# 01_BQ25895_BMS.net
KiCad netlist of a schematic drawn in Altium Designer
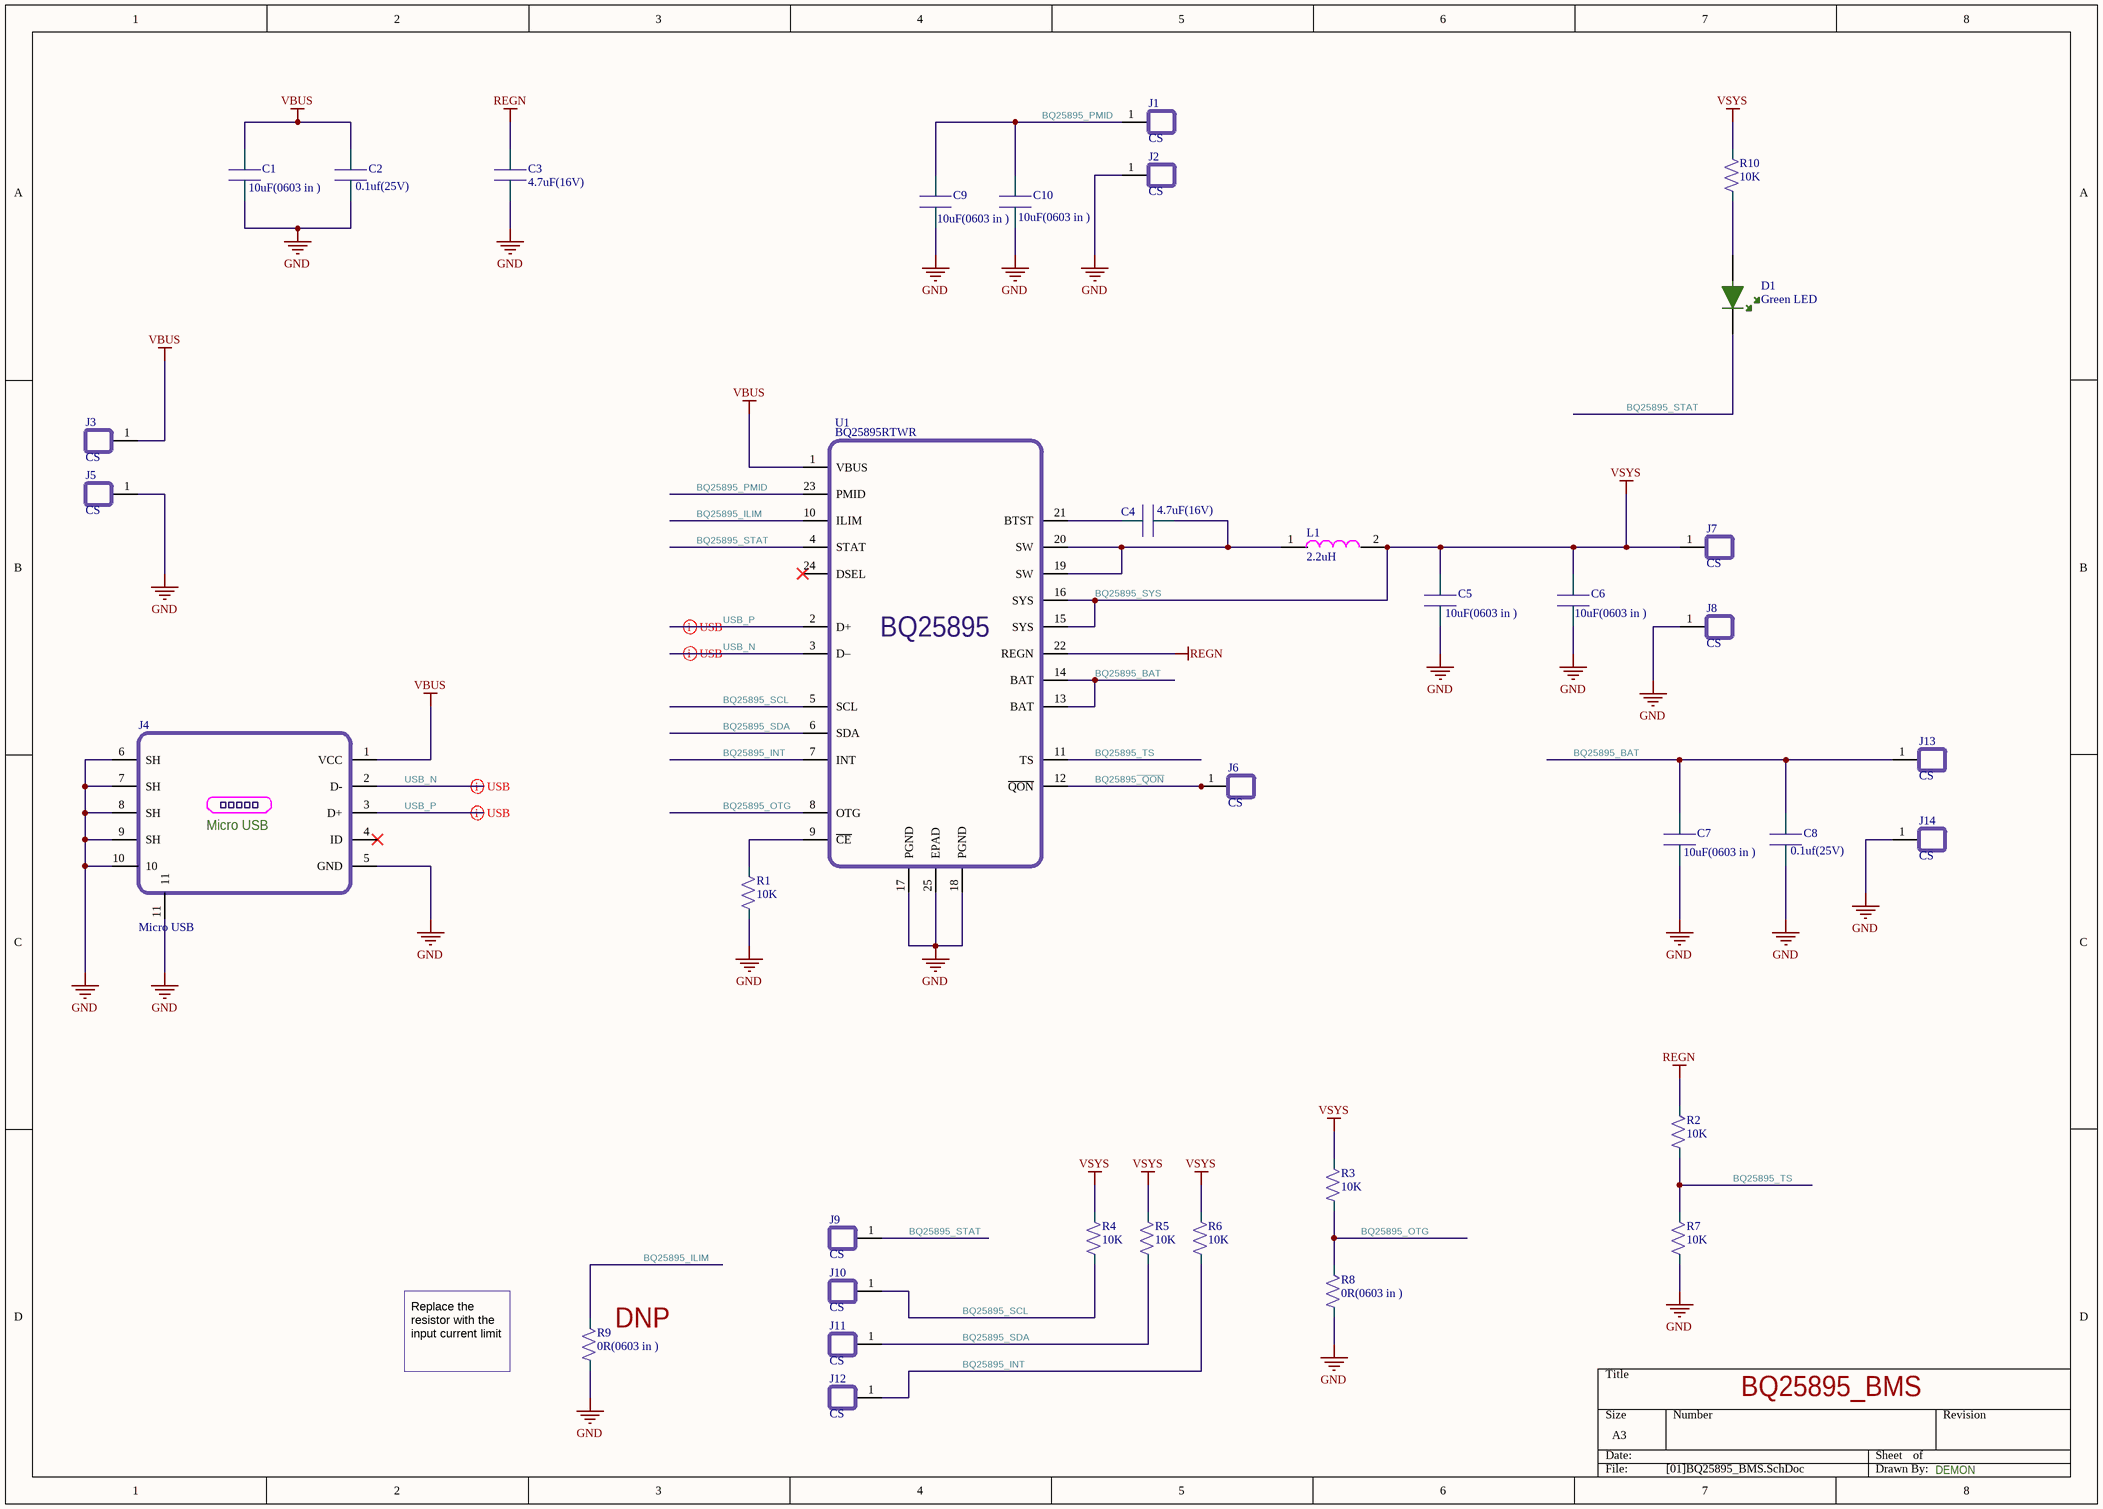
[diagram p0: [01]BQ25895_BMS.SchDoc]

(export (version "E")
  (design (tool "Eeschema 10.0.6"))
  (components
    (comp (ref "C1")
      (value "10uF(0603 in )")
      (footprint "Capacitor_0603")
      (description "10µF ±10% 25V Ceramic Capacitor X5R 0603 (1608 Metric)")
      (fields
        (field (name "MANUFACTURERPARTNUMBER") "GRM188R61E106KA73D")
        (field (name "MANUFACTURER") "Murata Electronics")
      )
      (libsource (lib "Capacitors") (part "GRM188R61E106KA73D"))
    )
    (comp (ref "C2")
      (value "0.1uf(25V)")
      (footprint "Capacitor_0603")
      (description "±5% 25V Ceramic Capacitor X7R 0603 (1608 Metric)")
      (fields
        (field (name "MANUFACTURERPARTNUMBER") "C0603C104J3RAC7411")
        (field (name "MANUFACTURER") "KEMET")
      )
      (libsource (lib "Capacitors") (part "C0603C104J3RAC7411"))
    )
    (comp (ref "C3")
      (value "4.7uF(16V)")
      (footprint "Capacitor_0603")
      (description "4.7µF ±10% 16V Ceramic Capacitor X7S 0603 (1608 Metric)")
      (fields
        (field (name "MANUFACTURERPARTNUMBER") "GRM188C71C475KE21D")
        (field (name "MANUFACTURER") "Murata Electronics")
      )
      (libsource (lib "Capacitors") (part "GRM188C71C475KE21D"))
    )
    (comp (ref "C4")
      (value "4.7uF(16V)")
      (footprint "CAPACITOR_0402")
      (description "4.7µF ±20% 16V Ceramic Capacitor X5R 0402 (1005 Metric)")
      (fields
        (field (name "MANUFACTURERPARTNUMBER") "0402YD475MAT2A")
        (field (name "MANUFACTURER") "AVX Corporation")
      )
      (libsource (lib "Capacitors") (part "0402YD475MAT2A"))
    )
    (comp (ref "C5")
      (value "10uF(0603 in )")
      (footprint "Capacitor_0603")
      (description "10µF ±10% 25V Ceramic Capacitor X5R 0603 (1608 Metric)")
      (fields
        (field (name "MANUFACTURERPARTNUMBER") "GRM188R61E106KA73D")
        (field (name "MANUFACTURER") "Murata Electronics")
      )
      (libsource (lib "Capacitors") (part "GRM188R61E106KA73D"))
    )
    (comp (ref "C6")
      (value "10uF(0603 in )")
      (footprint "Capacitor_0603")
      (description "10µF ±10% 25V Ceramic Capacitor X5R 0603 (1608 Metric)")
      (fields
        (field (name "MANUFACTURERPARTNUMBER") "GRM188R61E106KA73D")
        (field (name "MANUFACTURER") "Murata Electronics")
      )
      (libsource (lib "Capacitors") (part "GRM188R61E106KA73D"))
    )
    (comp (ref "C7")
      (value "10uF(0603 in )")
      (footprint "Capacitor_0603")
      (description "10µF ±10% 25V Ceramic Capacitor X5R 0603 (1608 Metric)")
      (fields
        (field (name "MANUFACTURERPARTNUMBER") "GRM188R61E106KA73D")
        (field (name "MANUFACTURER") "Murata Electronics")
      )
      (libsource (lib "Capacitors") (part "GRM188R61E106KA73D"))
    )
    (comp (ref "C8")
      (value "0.1uf(25V)")
      (footprint "Capacitor_0603")
      (description "±5% 25V Ceramic Capacitor X7R 0603 (1608 Metric)")
      (fields
        (field (name "MANUFACTURERPARTNUMBER") "C0603C104J3RAC7411")
        (field (name "MANUFACTURER") "KEMET")
      )
      (libsource (lib "Capacitors") (part "C0603C104J3RAC7411"))
    )
    (comp (ref "C9")
      (value "10uF(0603 in )")
      (footprint "Capacitor_0603")
      (description "10µF ±10% 25V Ceramic Capacitor X5R 0603 (1608 Metric)")
      (fields
        (field (name "MANUFACTURERPARTNUMBER") "GRM188R61E106KA73D")
        (field (name "MANUFACTURER") "Murata Electronics")
      )
      (libsource (lib "Capacitors") (part "GRM188R61E106KA73D"))
    )
    (comp (ref "C10")
      (value "10uF(0603 in )")
      (footprint "Capacitor_0603")
      (description "10µF ±10% 25V Ceramic Capacitor X5R 0603 (1608 Metric)")
      (fields
        (field (name "MANUFACTURERPARTNUMBER") "GRM188R61E106KA73D")
        (field (name "MANUFACTURER") "Murata Electronics")
      )
      (libsource (lib "Capacitors") (part "GRM188R61E106KA73D"))
    )
    (comp (ref "D1")
      (value "Green LED")
      (footprint "0603_LED")
      (description "Green 570nm LED Indication - Discrete 1.7V 0603 (1608 Metric)")
      (fields (field (name "MANUFACTURERPARTNUMBER") "APHD1608LZGCK"))
      (libsource (lib "Diodes") (part "APHD1608LZGCK"))
    )
    (comp (ref "J1")
      (value "CS")
      (footprint "castellated_small")
      (libsource (lib "connectors") (part "castellated_Small"))
    )
    (comp (ref "J2")
      (value "CS")
      (footprint "castellated_small")
      (libsource (lib "connectors") (part "castellated_Small"))
    )
    (comp (ref "J3")
      (value "CS")
      (footprint "castellated_small")
      (libsource (lib "connectors") (part "castellated_Small"))
    )
    (comp (ref "J4")
      (value "Micro USB")
      (footprint "TE_1981568-1")
      (description "USB - micro B USB 2.0 Receptacle Connector 5 Position Surface Mount, Right Angle")
      (fields
        (field (name "MANUFACTURERPARTNUMBER") "1981568-1")
        (field (name "MANUFACTURER") "TE Connectivity AMP Connectors")
      )
      (libsource (lib "connectors") (part "1981568-1"))
    )
    (comp (ref "J5")
      (value "CS")
      (footprint "castellated_small")
      (libsource (lib "connectors") (part "castellated_Small"))
    )
    (comp (ref "J6")
      (value "CS")
      (footprint "castellated_small")
      (libsource (lib "connectors") (part "castellated_Small"))
    )
    (comp (ref "J7")
      (value "CS")
      (footprint "castellated_small")
      (libsource (lib "connectors") (part "castellated_Small"))
    )
    (comp (ref "J8")
      (value "CS")
      (footprint "castellated_small")
      (libsource (lib "connectors") (part "castellated_Small"))
    )
    (comp (ref "J9")
      (value "CS")
      (footprint "castellated_small")
      (libsource (lib "connectors") (part "castellated_Small"))
    )
    (comp (ref "J10")
      (value "CS")
      (footprint "castellated_small")
      (libsource (lib "connectors") (part "castellated_Small"))
    )
    (comp (ref "J11")
      (value "CS")
      (footprint "castellated_small")
      (libsource (lib "connectors") (part "castellated_Small"))
    )
    (comp (ref "J12")
      (value "CS")
      (footprint "castellated_small")
      (libsource (lib "connectors") (part "castellated_Small"))
    )
    (comp (ref "J13")
      (value "CS")
      (footprint "castellated_small")
      (libsource (lib "connectors") (part "castellated_Small"))
    )
    (comp (ref "J14")
      (value "CS")
      (footprint "castellated_small")
      (libsource (lib "connectors") (part "castellated_Small"))
    )
    (comp (ref "L1")
      (value "2.2uH")
      (footprint "22uh inductor")
      (description "FIXED IND 2.2UH 6.2A 15 MOHM SMD")
      (fields
        (field (name "MANUFACTURERPARTNUMBER") "7440650022")
        (field (name "MANUFACTURER") "Würth Elektronik")
      )
      (libsource (lib "Inductors and Coils") (part "7440650022"))
    )
    (comp (ref "R1")
      (value "10K")
      (footprint "RESISTOR0603")
      (description "10 kOhms ±5% 0.1W, 1/10W Chip Resistor 0603 (1608 Metric) Automotive AEC-Q200 Thick Film")
      (fields
        (field (name "MANUFACTURERPARTNUMBER") "RMCF0603JT10K0")
        (field (name "MANUFACTURER") "Stackpole Electronics Inc")
      )
      (libsource (lib "Resistors") (part "RMCF0603JT10K0"))
    )
    (comp (ref "R2")
      (value "10K")
      (footprint "RESISTOR0603")
      (description "10 kOhms ±5% 0.1W, 1/10W Chip Resistor 0603 (1608 Metric) Automotive AEC-Q200 Thick Film")
      (fields
        (field (name "MANUFACTURERPARTNUMBER") "RMCF0603JT10K0")
        (field (name "MANUFACTURER") "Stackpole Electronics Inc")
      )
      (libsource (lib "Resistors") (part "RMCF0603JT10K0"))
    )
    (comp (ref "R3")
      (value "10K")
      (footprint "RESISTOR0603")
      (description "10 kOhms ±5% 0.1W, 1/10W Chip Resistor 0603 (1608 Metric) Automotive AEC-Q200 Thick Film")
      (fields
        (field (name "MANUFACTURERPARTNUMBER") "RMCF0603JT10K0")
        (field (name "MANUFACTURER") "Stackpole Electronics Inc")
      )
      (libsource (lib "Resistors") (part "RMCF0603JT10K0"))
    )
    (comp (ref "R4")
      (value "10K")
      (footprint "RESISTOR0603")
      (description "10 kOhms ±5% 0.1W, 1/10W Chip Resistor 0603 (1608 Metric) Automotive AEC-Q200 Thick Film")
      (fields
        (field (name "MANUFACTURERPARTNUMBER") "RMCF0603JT10K0")
        (field (name "MANUFACTURER") "Stackpole Electronics Inc")
      )
      (libsource (lib "Resistors") (part "RMCF0603JT10K0"))
    )
    (comp (ref "R5")
      (value "10K")
      (footprint "RESISTOR0603")
      (description "10 kOhms ±5% 0.1W, 1/10W Chip Resistor 0603 (1608 Metric) Automotive AEC-Q200 Thick Film")
      (fields
        (field (name "MANUFACTURERPARTNUMBER") "RMCF0603JT10K0")
        (field (name "MANUFACTURER") "Stackpole Electronics Inc")
      )
      (libsource (lib "Resistors") (part "RMCF0603JT10K0"))
    )
    (comp (ref "R6")
      (value "10K")
      (footprint "RESISTOR0603")
      (description "10 kOhms ±5% 0.1W, 1/10W Chip Resistor 0603 (1608 Metric) Automotive AEC-Q200 Thick Film")
      (fields
        (field (name "MANUFACTURERPARTNUMBER") "RMCF0603JT10K0")
        (field (name "MANUFACTURER") "Stackpole Electronics Inc")
      )
      (libsource (lib "Resistors") (part "RMCF0603JT10K0"))
    )
    (comp (ref "R7")
      (value "10K")
      (footprint "RESISTOR0603")
      (description "10 kOhms ±5% 0.1W, 1/10W Chip Resistor 0603 (1608 Metric) Automotive AEC-Q200 Thick Film")
      (fields
        (field (name "MANUFACTURERPARTNUMBER") "RMCF0603JT10K0")
        (field (name "MANUFACTURER") "Stackpole Electronics Inc")
      )
      (libsource (lib "Resistors") (part "RMCF0603JT10K0"))
    )
    (comp (ref "R8")
      (value "0R(0603 in )")
      (footprint "RESISTOR0603")
      (description "0 Ohms Jumper 0.1W, 1/10W Chip Resistor 0603 (1608 Metric) Automotive AEC-Q200 Thick Film")
      (fields (field (name "MANUFACTURER PART NUMBER") "RMCF0603ZT0R00"))
      (libsource (lib "Resistors") (part "RMCF0603ZT0R00"))
    )
    (comp (ref "R9")
      (value "0R(0603 in )")
      (footprint "RESISTOR0603")
      (description "0 Ohms Jumper 0.1W, 1/10W Chip Resistor 0603 (1608 Metric) Automotive AEC-Q200 Thick Film")
      (fields (field (name "MANUFACTURER PART NUMBER") "RMCF0603ZT0R00"))
      (libsource (lib "Resistors") (part "RMCF0603ZT0R00"))
    )
    (comp (ref "R10")
      (value "10K")
      (footprint "RESISTOR0603")
      (description "10 kOhms ±5% 0.1W, 1/10W Chip Resistor 0603 (1608 Metric) Automotive AEC-Q200 Thick Film")
      (fields
        (field (name "MANUFACTURERPARTNUMBER") "RMCF0603JT10K0")
        (field (name "MANUFACTURER") "Stackpole Electronics Inc")
      )
      (libsource (lib "Resistors") (part "RMCF0603JT10K0"))
    )
    (comp (ref "U1")
      (value "BQ25895RTWR")
      (footprint "24-WQFN")
      (description "Charger IC Lithium Ion/Polymer 24-WQFN (4x4)")
      (fields (field (name "MANUFACTURER") "Texas Instruments"))
      (libsource (lib "integrated_circuits") (part "BQ25895RTWR"))
    )
  )
  (nets
    (net (code "1") (name "/BQ25895_BAT") (class "Default")
      (node (ref "C7") (pin "2") (pinfunction "2_2") (pintype "passive"))
      (node (ref "C8") (pin "2") (pinfunction "2_2") (pintype "passive"))
      (node (ref "J13") (pin "1") (pinfunction "1_1") (pintype "passive"))
      (node (ref "U1") (pin "13") (pinfunction "BAT_13") (pintype "passive"))
      (node (ref "U1") (pin "14") (pinfunction "BAT_14") (pintype "passive"))
    )
    (net (code "2") (name "/BQ25895_ILIM") (class "Default")
      (node (ref "R9") (pin "2") (pinfunction "2_2") (pintype "passive"))
      (node (ref "U1") (pin "10") (pinfunction "ILIM_10") (pintype "passive"))
    )
    (net (code "3") (name "/BQ25895_INT") (class "Default")
      (node (ref "J12") (pin "1") (pinfunction "1_1") (pintype "passive"))
      (node (ref "R6") (pin "1") (pinfunction "1_1") (pintype "passive"))
      (node (ref "U1") (pin "7") (pinfunction "INT_7") (pintype "passive"))
    )
    (net (code "4") (name "/BQ25895_OTG") (class "Default")
      (node (ref "R3") (pin "1") (pinfunction "1_1") (pintype "passive"))
      (node (ref "R8") (pin "2") (pinfunction "2_2") (pintype "passive"))
      (node (ref "U1") (pin "8") (pinfunction "OTG_8") (pintype "passive"))
    )
    (net (code "5") (name "/BQ25895_PMID") (class "Default")
      (node (ref "C10") (pin "2") (pinfunction "2_2") (pintype "passive"))
      (node (ref "C9") (pin "2") (pinfunction "2_2") (pintype "passive"))
      (node (ref "J1") (pin "1") (pinfunction "1_1") (pintype "passive"))
      (node (ref "U1") (pin "23") (pinfunction "PMID_23") (pintype "passive"))
    )
    (net (code "6") (name "/BQ25895_SCL") (class "Default")
      (node (ref "J10") (pin "1") (pinfunction "1_1") (pintype "passive"))
      (node (ref "R4") (pin "1") (pinfunction "1_1") (pintype "passive"))
      (node (ref "U1") (pin "5") (pinfunction "SCL_5") (pintype "passive"))
    )
    (net (code "7") (name "/BQ25895_SDA") (class "Default")
      (node (ref "J11") (pin "1") (pinfunction "1_1") (pintype "passive"))
      (node (ref "R5") (pin "1") (pinfunction "1_1") (pintype "passive"))
      (node (ref "U1") (pin "6") (pinfunction "SDA_6") (pintype "passive"))
    )
    (net (code "8") (name "/BQ25895_STAT") (class "Default")
      (node (ref "D1") (pin "2") (pinfunction "2_2") (pintype "passive"))
      (node (ref "J9") (pin "1") (pinfunction "1_1") (pintype "passive"))
      (node (ref "U1") (pin "4") (pinfunction "STAT_4") (pintype "passive"))
    )
    (net (code "9") (name "/BQ25895_TS") (class "Default")
      (node (ref "R2") (pin "1") (pinfunction "1_1") (pintype "passive"))
      (node (ref "R7") (pin "2") (pinfunction "2_2") (pintype "passive"))
      (node (ref "U1") (pin "11") (pinfunction "TS_11") (pintype "passive"))
    )
    (net (code "10") (name "/BQ25895~{_QON}") (class "Default")
      (node (ref "J6") (pin "1") (pinfunction "1_1") (pintype "passive"))
      (node (ref "U1") (pin "12") (pinfunction "~{QON}_12") (pintype "passive"))
    )
    (net (code "11") (name "/USB_N") (class "Default")
      (node (ref "J4") (pin "2") (pinfunction "D-_2") (pintype "passive"))
      (node (ref "U1") (pin "3") (pinfunction "D–_3") (pintype "passive"))
    )
    (net (code "12") (name "/USB_P") (class "Default")
      (node (ref "J4") (pin "3") (pinfunction "D+_3") (pintype "passive"))
      (node (ref "U1") (pin "2") (pinfunction "D+_2") (pintype "passive"))
    )
    (net (code "13") (name "GND") (class "Default")
      (node (ref "C1") (pin "1") (pinfunction "1_1") (pintype "passive"))
      (node (ref "C10") (pin "1") (pinfunction "1_1") (pintype "passive"))
      (node (ref "C2") (pin "1") (pinfunction "1_1") (pintype "passive"))
      (node (ref "C3") (pin "1") (pinfunction "1_1") (pintype "passive"))
      (node (ref "C5") (pin "1") (pinfunction "1_1") (pintype "passive"))
      (node (ref "C6") (pin "1") (pinfunction "1_1") (pintype "passive"))
      (node (ref "C7") (pin "1") (pinfunction "1_1") (pintype "passive"))
      (node (ref "C8") (pin "1") (pinfunction "1_1") (pintype "passive"))
      (node (ref "C9") (pin "1") (pinfunction "1_1") (pintype "passive"))
      (node (ref "J14") (pin "1") (pinfunction "1_1") (pintype "passive"))
      (node (ref "J2") (pin "1") (pinfunction "1_1") (pintype "passive"))
      (node (ref "J4") (pin "10") (pinfunction "10_10") (pintype "passive"))
      (node (ref "J4") (pin "11") (pinfunction "11_11") (pintype "passive"))
      (node (ref "J4") (pin "5") (pinfunction "GND_5") (pintype "passive"))
      (node (ref "J4") (pin "6") (pinfunction "SH_6") (pintype "passive"))
      (node (ref "J4") (pin "7") (pinfunction "SH_7") (pintype "passive"))
      (node (ref "J4") (pin "8") (pinfunction "SH_8") (pintype "passive"))
      (node (ref "J4") (pin "9") (pinfunction "SH_9") (pintype "passive"))
      (node (ref "J5") (pin "1") (pinfunction "1_1") (pintype "passive"))
      (node (ref "J8") (pin "1") (pinfunction "1_1") (pintype "passive"))
      (node (ref "R1") (pin "1") (pinfunction "1_1") (pintype "passive"))
      (node (ref "R7") (pin "1") (pinfunction "1_1") (pintype "passive"))
      (node (ref "R8") (pin "1") (pinfunction "1_1") (pintype "passive"))
      (node (ref "R9") (pin "1") (pinfunction "1_1") (pintype "passive"))
      (node (ref "U1") (pin "17") (pinfunction "PGND_17") (pintype "passive"))
      (node (ref "U1") (pin "18") (pinfunction "PGND_18") (pintype "passive"))
      (node (ref "U1") (pin "25") (pinfunction "EPAD_25") (pintype "passive"))
    )
    (net (code "14") (name "Net-(C4-Pad1)") (class "Default")
      (node (ref "C4") (pin "1") (pinfunction "1_1") (pintype "passive"))
      (node (ref "L1") (pin "1") (pinfunction "1_1") (pintype "passive"))
      (node (ref "U1") (pin "19") (pinfunction "SW_19") (pintype "passive"))
      (node (ref "U1") (pin "20") (pinfunction "SW_20") (pintype "passive"))
    )
    (net (code "15") (name "Net-(D1-Pad1)") (class "Default")
      (node (ref "D1") (pin "1") (pinfunction "1_1") (pintype "passive"))
      (node (ref "R10") (pin "1") (pinfunction "1_1") (pintype "passive"))
    )
    (net (code "16") (name "Net-(U1-BTST)") (class "Default")
      (node (ref "C4") (pin "2") (pinfunction "2_2") (pintype "passive"))
      (node (ref "U1") (pin "21") (pinfunction "BTST_21") (pintype "passive"))
    )
    (net (code "17") (name "Net-(U1-~{CE})") (class "Default")
      (node (ref "R1") (pin "2") (pinfunction "2_2") (pintype "passive"))
      (node (ref "U1") (pin "9") (pinfunction "~{CE}_9") (pintype "passive"))
    )
    (net (code "18") (name "REGN") (class "Default")
      (node (ref "C3") (pin "2") (pinfunction "2_2") (pintype "passive"))
      (node (ref "R2") (pin "2") (pinfunction "2_2") (pintype "passive"))
      (node (ref "U1") (pin "22") (pinfunction "REGN_22") (pintype "passive"))
    )
    (net (code "19") (name "VBUS") (class "Default")
      (node (ref "C1") (pin "2") (pinfunction "2_2") (pintype "passive"))
      (node (ref "C2") (pin "2") (pinfunction "2_2") (pintype "passive"))
      (node (ref "J3") (pin "1") (pinfunction "1_1") (pintype "passive"))
      (node (ref "J4") (pin "1") (pinfunction "VCC_1") (pintype "passive"))
      (node (ref "U1") (pin "1") (pinfunction "VBUS_1") (pintype "passive"))
    )
    (net (code "20") (name "VSYS") (class "Default")
      (node (ref "C5") (pin "2") (pinfunction "2_2") (pintype "passive"))
      (node (ref "C6") (pin "2") (pinfunction "2_2") (pintype "passive"))
      (node (ref "J7") (pin "1") (pinfunction "1_1") (pintype "passive"))
      (node (ref "L1") (pin "2") (pinfunction "2_2") (pintype "passive"))
      (node (ref "R10") (pin "2") (pinfunction "2_2") (pintype "passive"))
      (node (ref "R3") (pin "2") (pinfunction "2_2") (pintype "passive"))
      (node (ref "R4") (pin "2") (pinfunction "2_2") (pintype "passive"))
      (node (ref "R5") (pin "2") (pinfunction "2_2") (pintype "passive"))
      (node (ref "R6") (pin "2") (pinfunction "2_2") (pintype "passive"))
      (node (ref "U1") (pin "15") (pinfunction "SYS_15") (pintype "passive"))
      (node (ref "U1") (pin "16") (pinfunction "SYS_16") (pintype "passive"))
    )
    (net (code "21") (name "unconnected-(J4-ID-Pad4)") (class "Default")
      (node (ref "J4") (pin "4") (pinfunction "ID_4") (pintype "passive+no_connect"))
    )
    (net (code "22") (name "unconnected-(U1-DSEL-Pad24)") (class "Default")
      (node (ref "U1") (pin "24") (pinfunction "DSEL_24") (pintype "passive+no_connect"))
    )
  )
)
